# RedBot_Whisker_Bumper.net
KiCad netlist of a schematic drawn in EAGLE
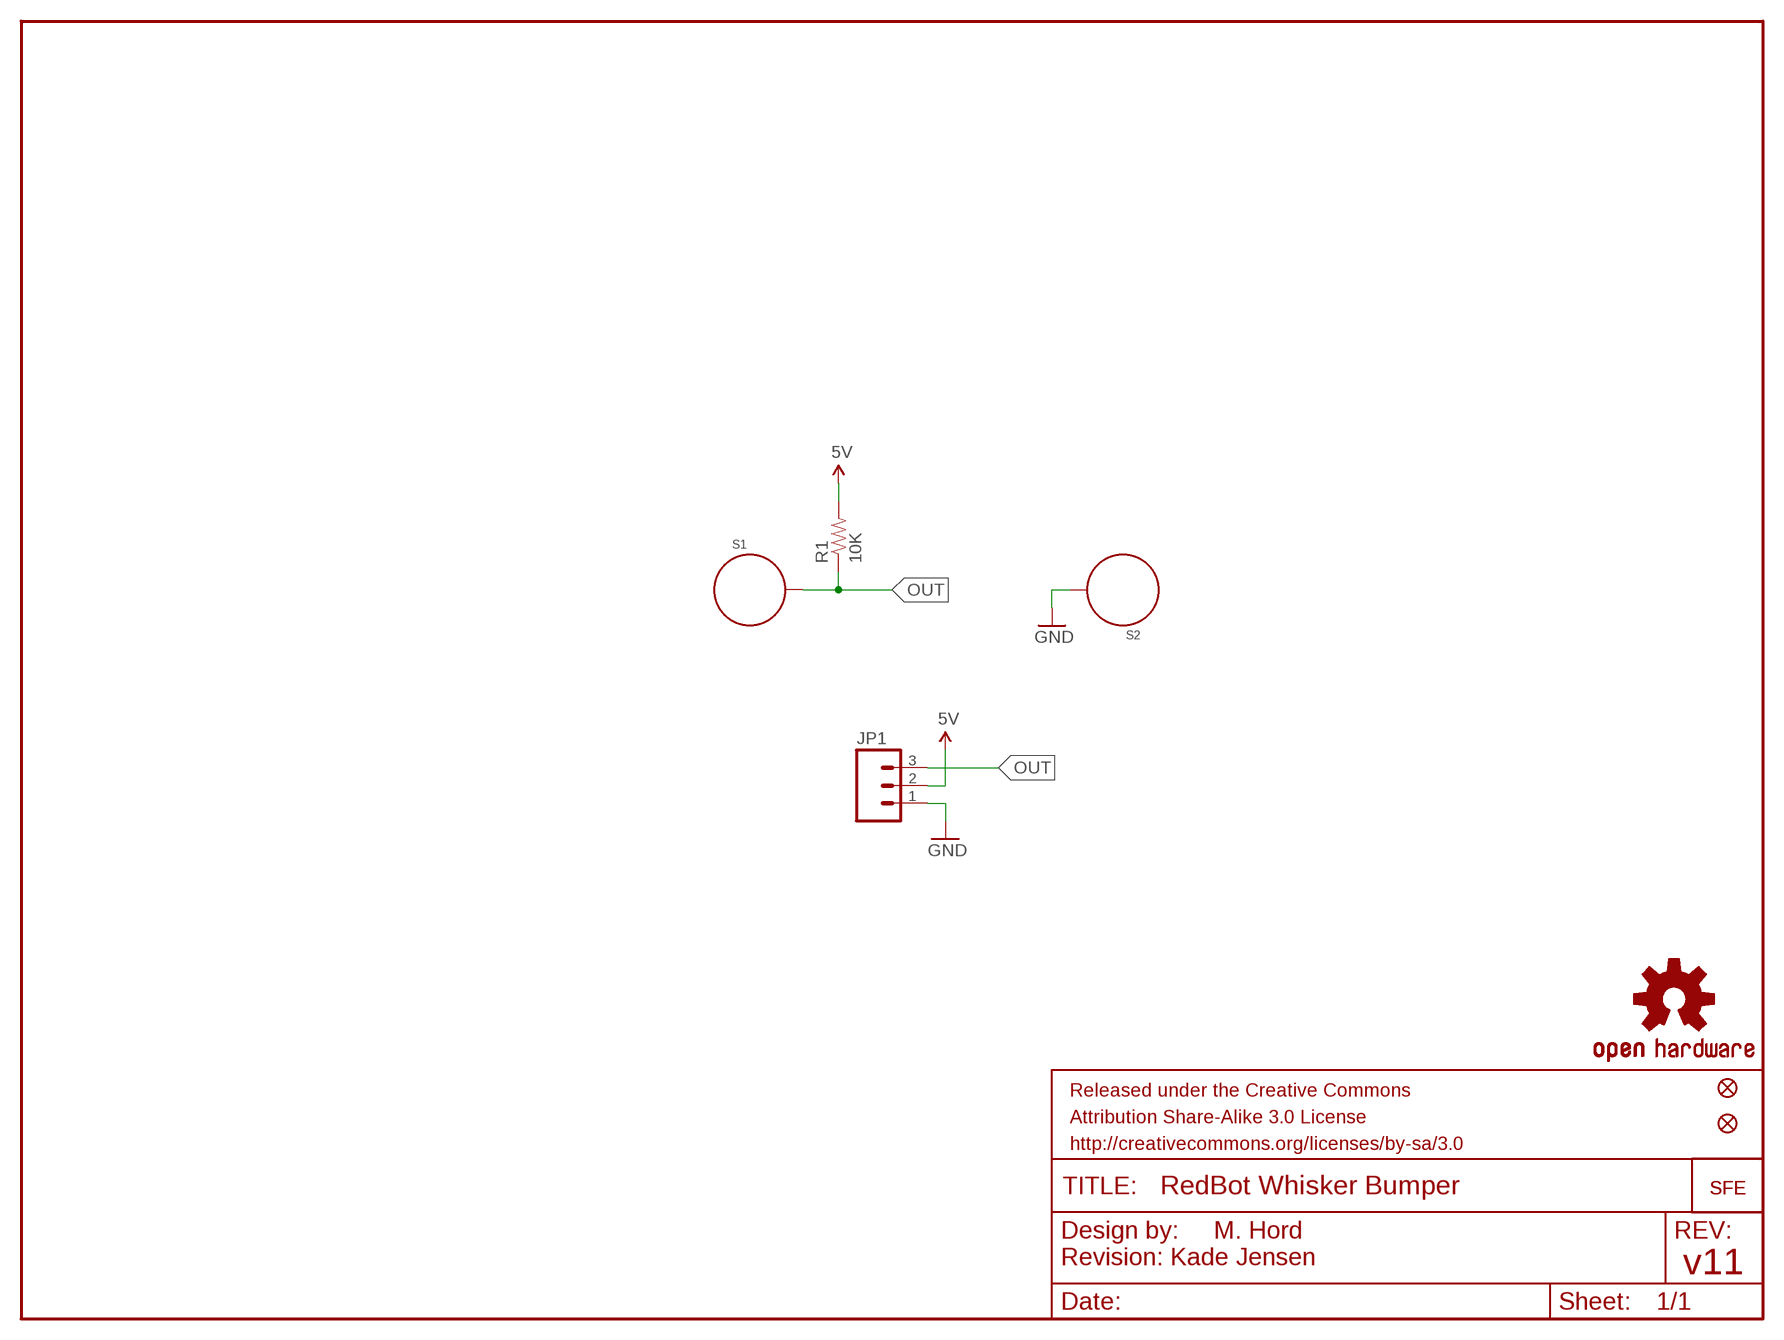
[diagram p0: schematic, sheet 1]

(export (version "E")
  (design (tool "Eeschema 10.0.6"))
  (components
    (comp (ref "FID1")
      (value "FIDUCIALUFIDUCIAL")
      (footprint "eagle-import:MICRO-FIDUCIAL")
      (libsource (lib "eagle-import") (part "FIDUCIALUFIDUCIAL"))
    )
    (comp (ref "FID2")
      (value "FIDUCIALUFIDUCIAL")
      (footprint "eagle-import:MICRO-FIDUCIAL")
      (libsource (lib "eagle-import") (part "FIDUCIALUFIDUCIAL"))
    )
    (comp (ref "FRAME1")
      (value "FRAME-LETTER")
      (footprint "eagle-import:CREATIVE_COMMONS")
      (libsource (lib "eagle-import") (part "FRAME-LETTER"))
    )
    (comp (ref "JP1")
      (value "M03SMD_RA_MALE_POST")
      (footprint "eagle-import:1X03_SMD_RA_MALE_POST")
      (libsource (lib "eagle-import") (part "M03SMD_RA_MALE_POST"))
    )
    (comp (ref "LOGO1")
      (value "OSHW-LOGOS")
      (footprint "eagle-import:OSHW-LOGO-S")
      (libsource (lib "eagle-import") (part "OSHW-LOGOS"))
    )
    (comp (ref "LOGO2")
      (value "LOGO-SFESK")
      (footprint "eagle-import:SFE-LOGO-FLAME")
      (libsource (lib "eagle-import") (part "LOGO-SFESK"))
    )
    (comp (ref "LOGO3")
      (value "OSHW-LOGOS")
      (footprint "eagle-import:OSHW-LOGO-S")
      (libsource (lib "eagle-import") (part "OSHW-LOGOS"))
    )
    (comp (ref "LOGO4")
      (value "LOGO-SFESK")
      (footprint "eagle-import:SFE-LOGO-FLAME")
      (libsource (lib "eagle-import") (part "LOGO-SFESK"))
    )
    (comp (ref "R1")
      (value "10K")
      (footprint "eagle-import:0603-RES")
      (libsource (lib "eagle-import") (part "10KOHM1/10W1%(0603)0603"))
    )
    (comp (ref "S1")
      (value "STANDOFF_ELECTRICAL")
      (footprint "eagle-import:STANDOFF-ELECTRICAL")
      (libsource (lib "eagle-import") (part "STANDOFF_ELECTRICAL"))
    )
    (comp (ref "S2")
      (value "STANDOFF_ELECTRICAL")
      (footprint "eagle-import:STANDOFF-ELECTRICAL")
      (libsource (lib "eagle-import") (part "STANDOFF_ELECTRICAL"))
    )
  )
  (nets
    (net (code "1") (name "5V") (class "Default")
      (node (ref "JP1") (pin "2") (pinfunction "2_2") (pintype "passive"))
      (node (ref "R1") (pin "2") (pinfunction "2_2") (pintype "passive"))
    )
    (net (code "2") (name "GND") (class "Default")
      (node (ref "JP1") (pin "1") (pinfunction "1_1") (pintype "passive"))
      (node (ref "S2") (pin "P1") (pinfunction "P$1_P1") (pintype "bidirectional"))
    )
    (net (code "3") (name "OUT") (class "Default")
      (node (ref "JP1") (pin "3") (pinfunction "3_3") (pintype "passive"))
      (node (ref "R1") (pin "1") (pinfunction "1_1") (pintype "passive"))
      (node (ref "S1") (pin "P1") (pinfunction "P$1_P1") (pintype "bidirectional"))
    )
  )
)
